# usbschem.net
KiCad netlist of a schematic drawn in EasyEDA
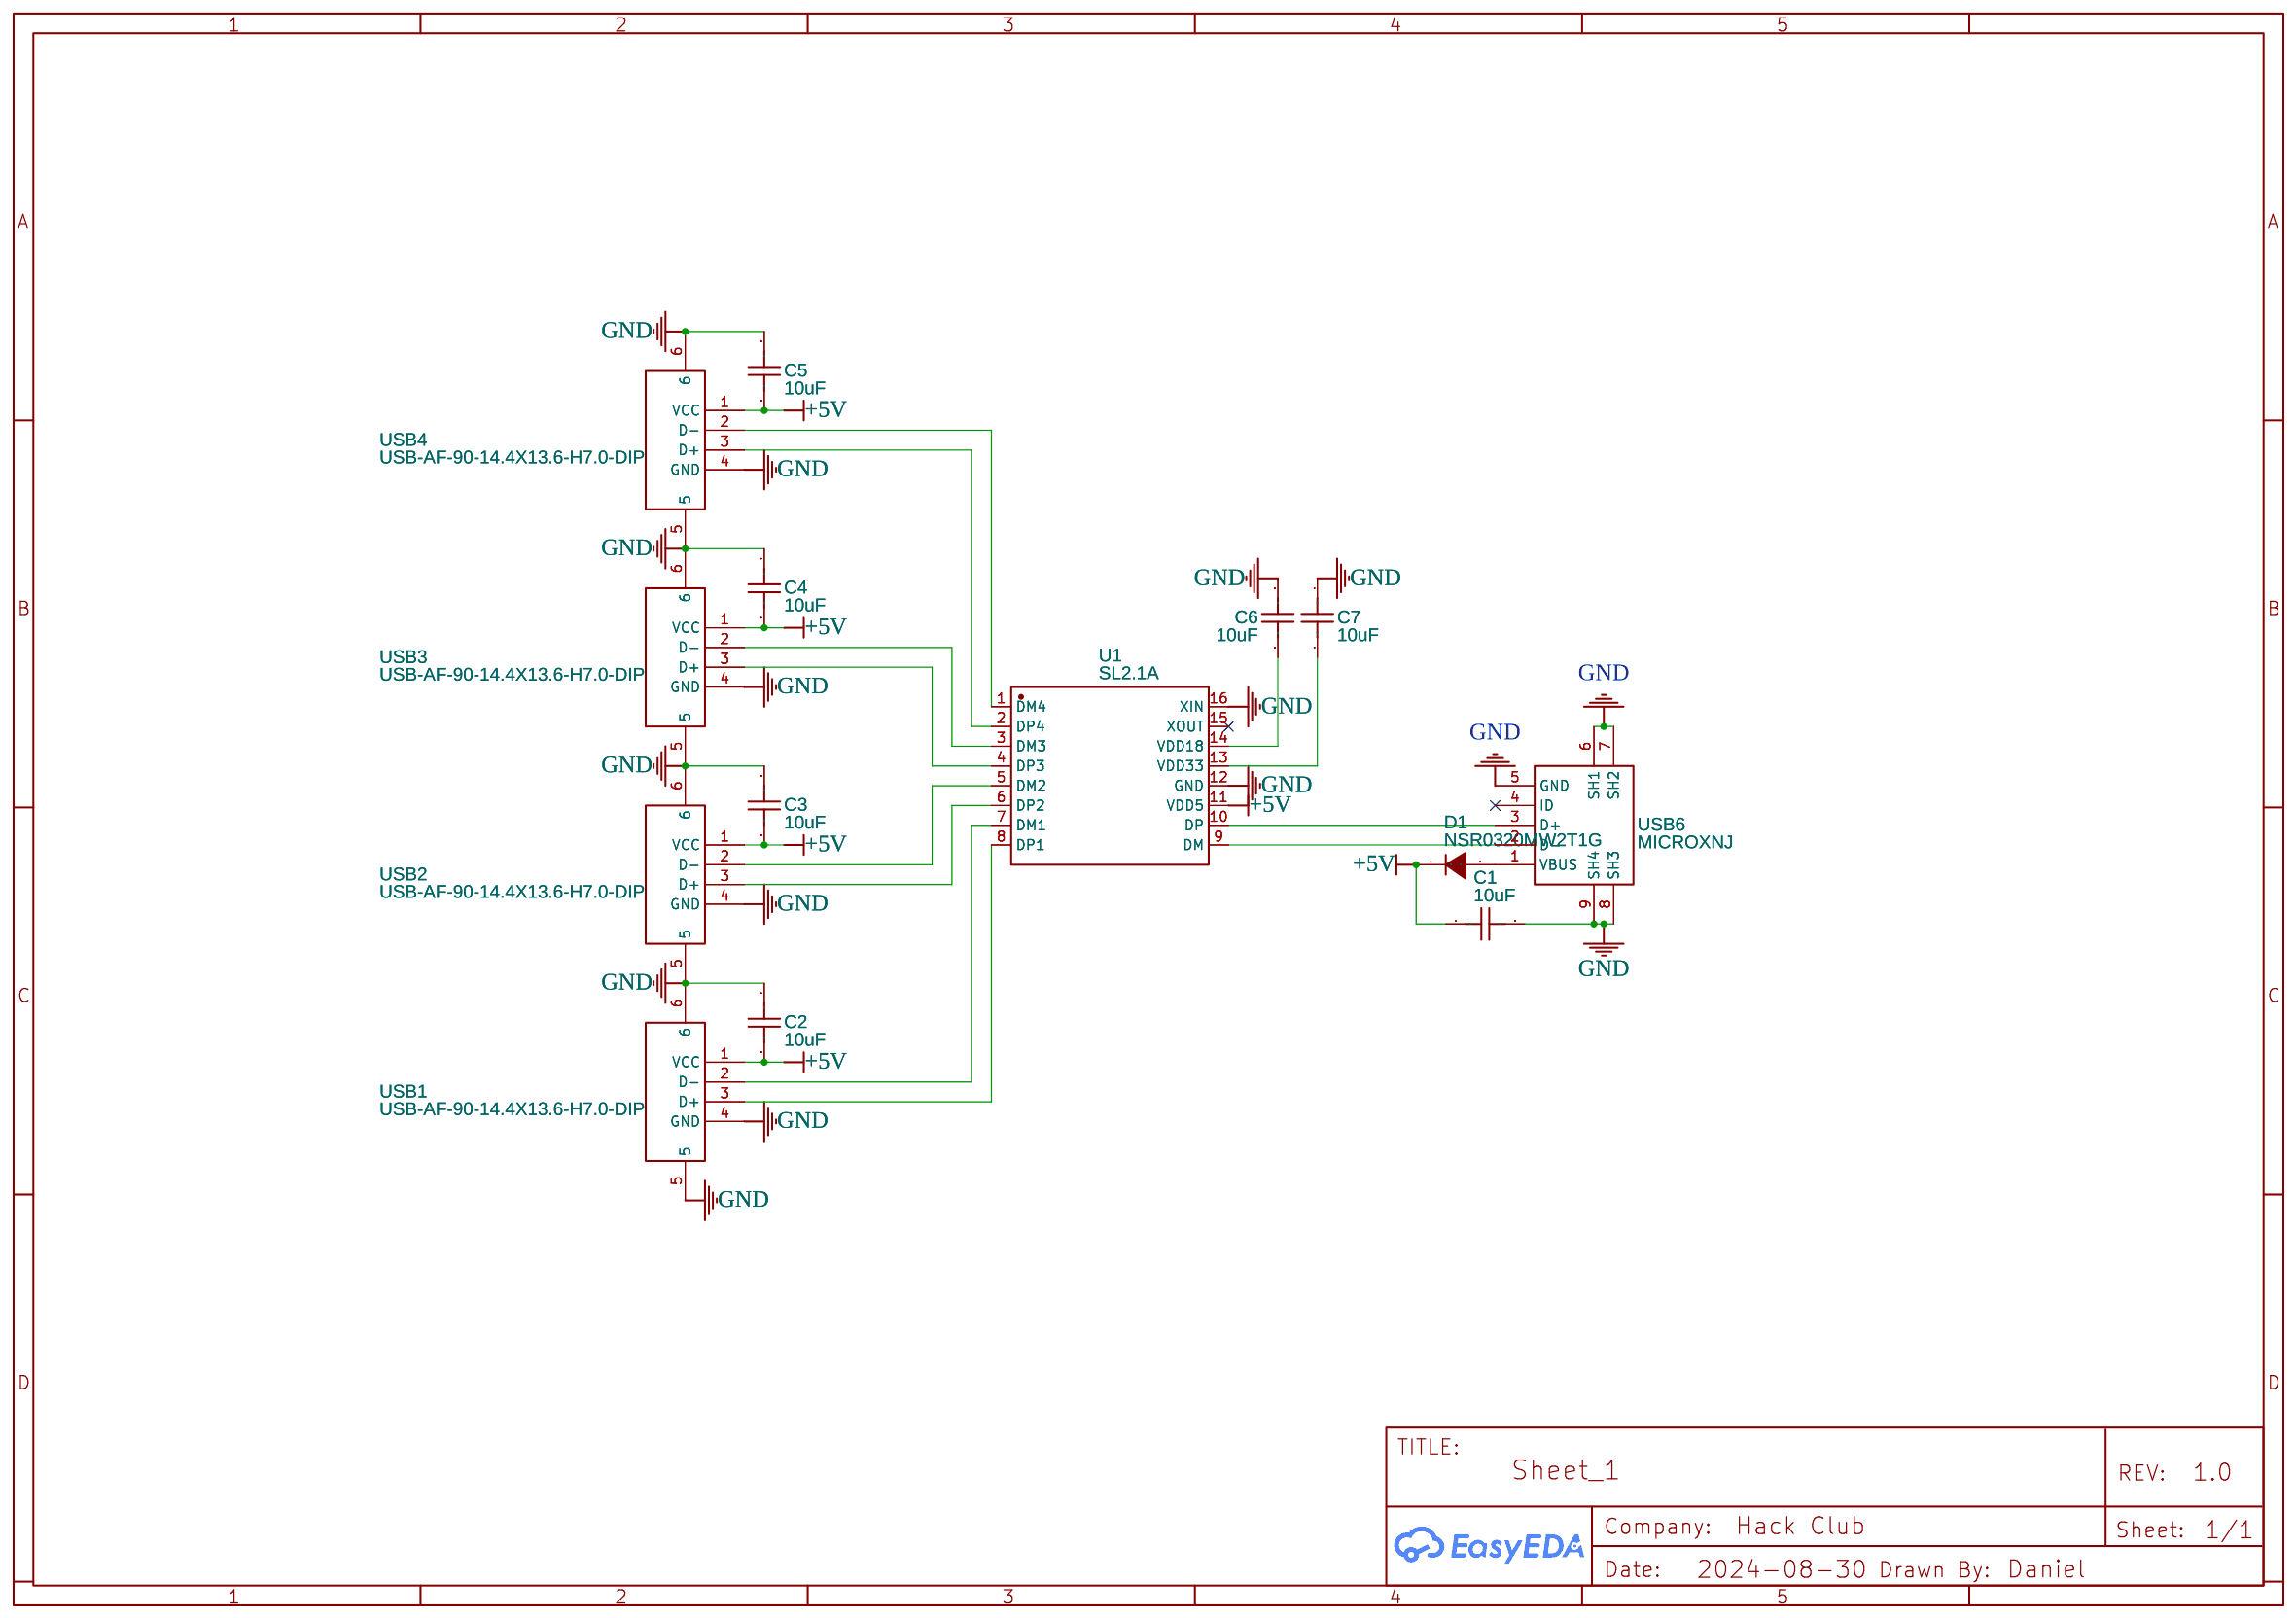
[diagram p0: schematic sheet]

(export (version "E")
  (design (tool "Eeschema 10.0.6"))
  (components
    (comp (ref "C1")
      (value "10uF")
      (fields
        (field (name "Manufacturer Part") "CL10A106KP8NNNC")
        (field (name "Manufacturer") "SAMSUNG(三星)")
      )
      (libsource (lib "") (part "CL10A106KP8NNNC_1"))
    )
    (comp (ref "C2")
      (value "10uF")
      (fields
        (field (name "Manufacturer Part") "CL10A106KP8NNNC")
        (field (name "Manufacturer") "SAMSUNG(三星)")
      )
      (libsource (lib "") (part "CL10A106KP8NNNC"))
    )
    (comp (ref "C3")
      (value "10uF")
      (fields
        (field (name "Manufacturer Part") "CL10A106KP8NNNC")
        (field (name "Manufacturer") "SAMSUNG(三星)")
      )
      (libsource (lib "") (part "CL10A106KP8NNNC"))
    )
    (comp (ref "C4")
      (value "10uF")
      (fields
        (field (name "Manufacturer Part") "CL10A106KP8NNNC")
        (field (name "Manufacturer") "SAMSUNG(三星)")
      )
      (libsource (lib "") (part "CL10A106KP8NNNC"))
    )
    (comp (ref "C5")
      (value "10uF")
      (fields
        (field (name "Manufacturer Part") "CL10A106KP8NNNC")
        (field (name "Manufacturer") "SAMSUNG(三星)")
      )
      (libsource (lib "") (part "CL10A106KP8NNNC"))
    )
    (comp (ref "C6")
      (value "10uF")
      (fields
        (field (name "Manufacturer Part") "CL10A106KP8NNNC")
        (field (name "Manufacturer") "SAMSUNG(三星)")
      )
      (libsource (lib "") (part "CL10A106KP8NNNC_2"))
    )
    (comp (ref "C7")
      (value "10uF")
      (fields
        (field (name "Manufacturer Part") "CL10A106KP8NNNC")
        (field (name "Manufacturer") "SAMSUNG(三星)")
      )
      (libsource (lib "") (part "CL10A106KP8NNNC"))
    )
    (comp (ref "D1")
      (value "NSR0320MW2T1G")
      (fields (field (name "Manufacturer") "onsemi(安森美)"))
      (libsource (lib "") (part "NSR0320MW2T1G"))
    )
    (comp (ref "U1")
      (value "SL2.1A")
      (fields (field (name "Manufacturer") "CoreChips(和芯润德)"))
      (libsource (lib "") (part "SL2.1A"))
    )
    (comp (ref "USB1")
      (value "USB-AF-90-14.4X13.6-H7.0-DIP")
      (fields (field (name "Manufacturer Part") "903-131A1011D10100") (field (name "Manufacturer") "精拓金"))
      (libsource (lib "") (part "USB-AF-90-14.4X13.6-H7.0-DIP"))
    )
    (comp (ref "USB2")
      (value "USB-AF-90-14.4X13.6-H7.0-DIP")
      (fields (field (name "Manufacturer Part") "903-131A1011D10100") (field (name "Manufacturer") "精拓金"))
      (libsource (lib "") (part "USB-AF-90-14.4X13.6-H7.0-DIP"))
    )
    (comp (ref "USB3")
      (value "USB-AF-90-14.4X13.6-H7.0-DIP")
      (fields (field (name "Manufacturer Part") "903-131A1011D10100") (field (name "Manufacturer") "精拓金"))
      (libsource (lib "") (part "USB-AF-90-14.4X13.6-H7.0-DIP"))
    )
    (comp (ref "USB4")
      (value "USB-AF-90-14.4X13.6-H7.0-DIP")
      (fields (field (name "Manufacturer Part") "903-131A1011D10100") (field (name "Manufacturer") "精拓金"))
      (libsource (lib "") (part "USB-AF-90-14.4X13.6-H7.0-DIP"))
    )
    (comp (ref "USB6")
      (value "MICROXNJ")
      (fields (field (name "Manufacturer Part") "MicroXNJ") (field (name "Manufacturer") "SHOU HAN(首韩)"))
      (libsource (lib "") (part "MICROXNJ"))
    )
  )
  (nets
    (net (code "1") (name "+5V") (class "Default")
      (node (ref "C1") (pin "1") (pinfunction "1_1") (pintype "unspecified"))
      (node (ref "C2") (pin "2") (pinfunction "2_2") (pintype "unspecified"))
      (node (ref "C3") (pin "2") (pinfunction "2_2") (pintype "unspecified"))
      (node (ref "C4") (pin "2") (pinfunction "2_2") (pintype "unspecified"))
      (node (ref "C5") (pin "2") (pinfunction "2_2") (pintype "unspecified"))
      (node (ref "D1") (pin "1") (pinfunction "C_1") (pintype "unspecified"))
      (node (ref "U1") (pin "11") (pinfunction "VDD5_11") (pintype "unspecified"))
      (node (ref "USB1") (pin "1") (pinfunction "VCC_1") (pintype "unspecified"))
      (node (ref "USB2") (pin "1") (pinfunction "VCC_1") (pintype "unspecified"))
      (node (ref "USB3") (pin "1") (pinfunction "VCC_1") (pintype "unspecified"))
      (node (ref "USB4") (pin "1") (pinfunction "VCC_1") (pintype "unspecified"))
    )
    (net (code "2") (name "GND") (class "Default")
      (node (ref "C1") (pin "2") (pinfunction "2_2") (pintype "unspecified"))
      (node (ref "C2") (pin "1") (pinfunction "1_1") (pintype "unspecified"))
      (node (ref "C3") (pin "1") (pinfunction "1_1") (pintype "unspecified"))
      (node (ref "C4") (pin "1") (pinfunction "1_1") (pintype "unspecified"))
      (node (ref "C5") (pin "1") (pinfunction "1_1") (pintype "unspecified"))
      (node (ref "C6") (pin "1") (pinfunction "1_1") (pintype "unspecified"))
      (node (ref "C7") (pin "1") (pinfunction "1_1") (pintype "unspecified"))
      (node (ref "U1") (pin "12") (pinfunction "GND_12") (pintype "unspecified"))
      (node (ref "U1") (pin "16") (pinfunction "XIN_16") (pintype "unspecified"))
      (node (ref "USB1") (pin "4") (pinfunction "GND_4") (pintype "unspecified"))
      (node (ref "USB1") (pin "5") (pinfunction "5_5") (pintype "unspecified"))
      (node (ref "USB1") (pin "6") (pinfunction "6_6") (pintype "unspecified"))
      (node (ref "USB2") (pin "4") (pinfunction "GND_4") (pintype "unspecified"))
      (node (ref "USB2") (pin "5") (pinfunction "5_5") (pintype "unspecified"))
      (node (ref "USB2") (pin "6") (pinfunction "6_6") (pintype "unspecified"))
      (node (ref "USB3") (pin "4") (pinfunction "GND_4") (pintype "unspecified"))
      (node (ref "USB3") (pin "5") (pinfunction "5_5") (pintype "unspecified"))
      (node (ref "USB3") (pin "6") (pinfunction "6_6") (pintype "unspecified"))
      (node (ref "USB4") (pin "4") (pinfunction "GND_4") (pintype "unspecified"))
      (node (ref "USB4") (pin "5") (pinfunction "5_5") (pintype "unspecified"))
      (node (ref "USB4") (pin "6") (pinfunction "6_6") (pintype "unspecified"))
      (node (ref "USB6") (pin "5") (pinfunction "GND_5") (pintype "unspecified"))
      (node (ref "USB6") (pin "6") (pinfunction "SH1_6") (pintype "unspecified"))
      (node (ref "USB6") (pin "7") (pinfunction "SH2_7") (pintype "unspecified"))
      (node (ref "USB6") (pin "8") (pinfunction "SH3_8") (pintype "unspecified"))
      (node (ref "USB6") (pin "9") (pinfunction "SH4_9") (pintype "unspecified"))
    )
    (net (code "3") (name "Net-(D1-A)") (class "Default")
      (node (ref "D1") (pin "2") (pinfunction "A_2") (pintype "unspecified"))
      (node (ref "USB6") (pin "1") (pinfunction "VBUS_1") (pintype "unspecified"))
    )
    (net (code "4") (name "Net-(U1-DM)") (class "Default")
      (node (ref "U1") (pin "9") (pinfunction "DM_9") (pintype "unspecified"))
      (node (ref "USB6") (pin "2") (pinfunction "D-_2") (pintype "unspecified"))
    )
    (net (code "5") (name "Net-(U1-DM1)") (class "Default")
      (node (ref "U1") (pin "7") (pinfunction "DM1_7") (pintype "unspecified"))
      (node (ref "USB1") (pin "2") (pinfunction "D-_2") (pintype "unspecified"))
    )
    (net (code "6") (name "Net-(U1-DM2)") (class "Default")
      (node (ref "U1") (pin "5") (pinfunction "DM2_5") (pintype "unspecified"))
      (node (ref "USB2") (pin "2") (pinfunction "D-_2") (pintype "unspecified"))
    )
    (net (code "7") (name "Net-(U1-DM3)") (class "Default")
      (node (ref "U1") (pin "3") (pinfunction "DM3_3") (pintype "unspecified"))
      (node (ref "USB3") (pin "2") (pinfunction "D-_2") (pintype "unspecified"))
    )
    (net (code "8") (name "Net-(U1-DM4)") (class "Default")
      (node (ref "U1") (pin "1") (pinfunction "DM4_1") (pintype "unspecified"))
      (node (ref "USB4") (pin "2") (pinfunction "D-_2") (pintype "unspecified"))
    )
    (net (code "9") (name "Net-(U1-DP)") (class "Default")
      (node (ref "U1") (pin "10") (pinfunction "DP_10") (pintype "unspecified"))
      (node (ref "USB6") (pin "3") (pinfunction "D+_3") (pintype "unspecified"))
    )
    (net (code "10") (name "Net-(U1-DP1)") (class "Default")
      (node (ref "U1") (pin "8") (pinfunction "DP1_8") (pintype "unspecified"))
      (node (ref "USB1") (pin "3") (pinfunction "D+_3") (pintype "unspecified"))
    )
    (net (code "11") (name "Net-(U1-DP2)") (class "Default")
      (node (ref "U1") (pin "6") (pinfunction "DP2_6") (pintype "unspecified"))
      (node (ref "USB2") (pin "3") (pinfunction "D+_3") (pintype "unspecified"))
    )
    (net (code "12") (name "Net-(U1-DP3)") (class "Default")
      (node (ref "U1") (pin "4") (pinfunction "DP3_4") (pintype "unspecified"))
      (node (ref "USB3") (pin "3") (pinfunction "D+_3") (pintype "unspecified"))
    )
    (net (code "13") (name "Net-(U1-DP4)") (class "Default")
      (node (ref "U1") (pin "2") (pinfunction "DP4_2") (pintype "unspecified"))
      (node (ref "USB4") (pin "3") (pinfunction "D+_3") (pintype "unspecified"))
    )
    (net (code "14") (name "Net-(U1-VDD18)") (class "Default")
      (node (ref "C6") (pin "2") (pinfunction "2_2") (pintype "unspecified"))
      (node (ref "U1") (pin "14") (pinfunction "VDD18_14") (pintype "unspecified"))
    )
    (net (code "15") (name "Net-(U1-VDD33)") (class "Default")
      (node (ref "C7") (pin "2") (pinfunction "2_2") (pintype "unspecified"))
      (node (ref "U1") (pin "13") (pinfunction "VDD33_13") (pintype "unspecified"))
    )
    (net (code "16") (name "unconnected-(U1-XOUT-Pad15)") (class "Default")
      (node (ref "U1") (pin "15") (pinfunction "XOUT_15") (pintype "unspecified+no_connect"))
    )
    (net (code "17") (name "unconnected-(USB6-ID-Pad4)") (class "Default")
      (node (ref "USB6") (pin "4") (pinfunction "ID_4") (pintype "unspecified+no_connect"))
    )
  )
)
